# MCU.net
KiCad netlist of a schematic drawn in Altium Designer
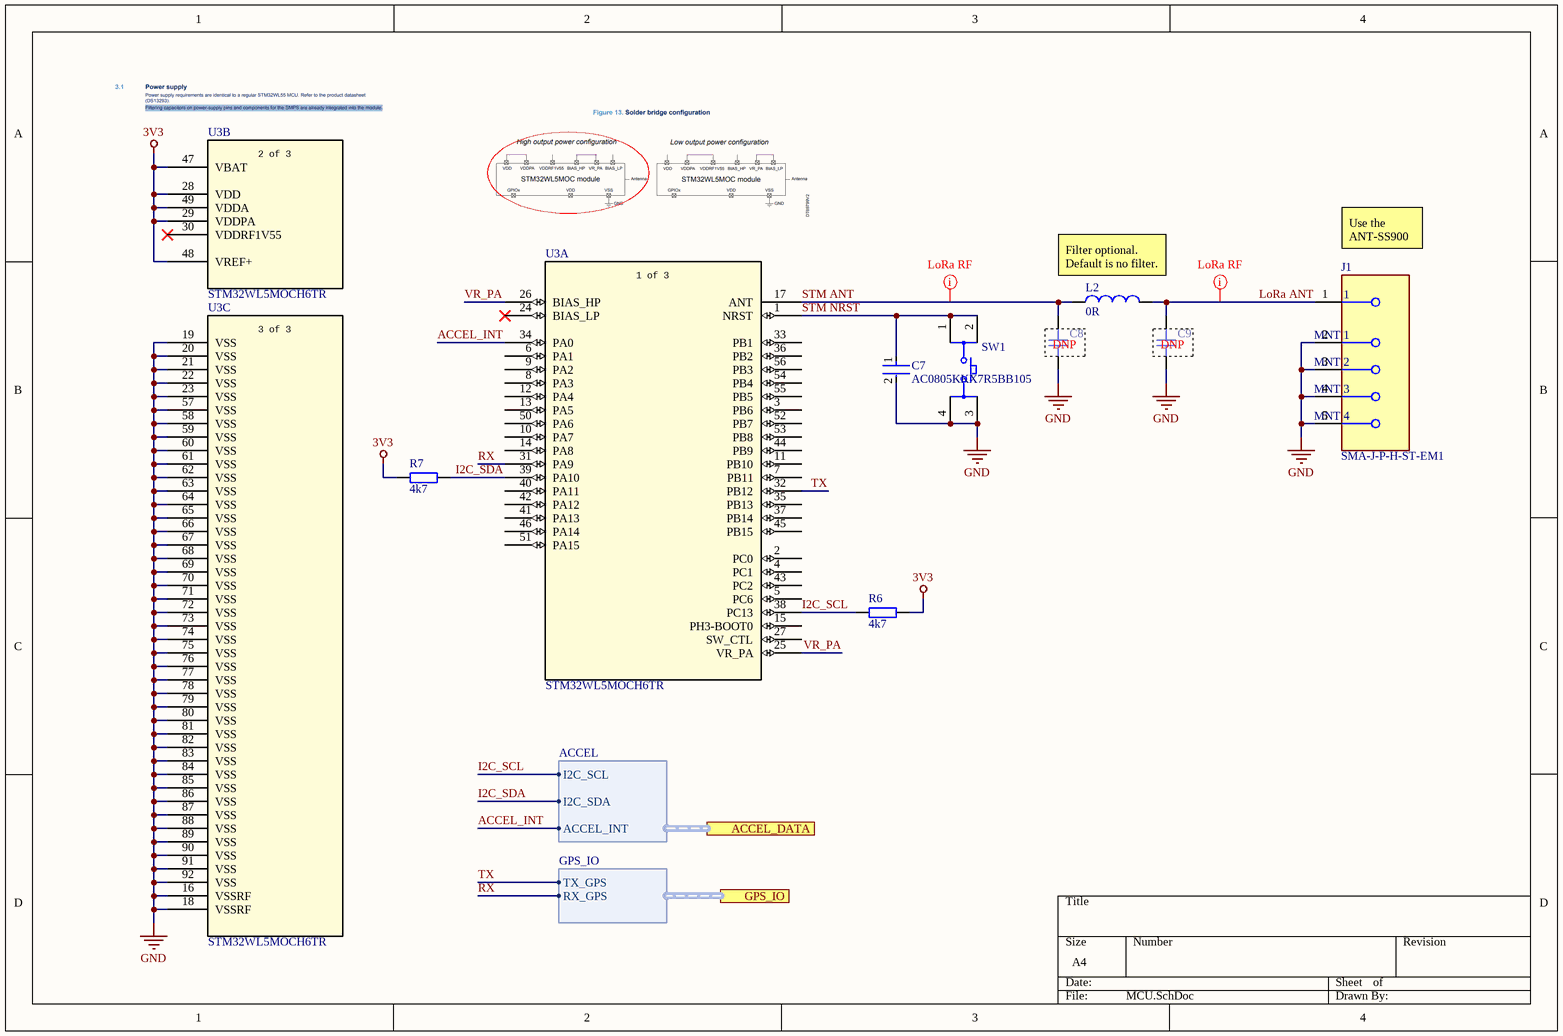
[diagram p0: MCU.SchDoc]

(export (version "E")
  (design (tool "Eeschema 10.0.6"))
  (components
    (comp (ref "C7")
      (value "AC0805KKX7R5BB105")
      (footprint "FP-AC0805-0_85-MFG")
      (description "AC0805 1 uF X7R 10.00% 6.3 V")
      (fields
        (field (name "OCTOPART") "https://octopart.com/ac0805kkx7r5bb105-yageo-78873385")
        (field (name "TOLERANCE") "0.1")
      )
      (libsource (lib "Altium Content Vault") (part "11868f565c42a9108669ba33697ecf6"))
    )
    (comp (ref "C8")
      (value "~")
      (footprint "CAP_0603")
      (description "Capacitor SMD 0603\r\nCeramic")
      (libsource (lib "Generic library") (part "CAP_0603"))
    )
    (comp (ref "C9")
      (value "~")
      (footprint "CAP_0603")
      (description "Capacitor SMD 0603\r\nCeramic")
      (libsource (lib "Generic library") (part "CAP_0603"))
    )
    (comp (ref "J1")
      (value "SMA-J-P-H-ST-EM1")
      (footprint "FP-SMA-J-P-H-ST-EM1-MFG")
      (description "CONN SMA JACK STR 50OHM EDGE MNT\r\nUse the ANT-SS900")
      (libsource (lib "Schlib1") (part "LoRa antenna connector"))
    )
    (comp (ref "L2")
      (value "0R")
      (footprint "CAP_0603")
      (description "Not necessary. Place 0 ohm resistor")
      (fields (field (name "MP") "LQG18HN27NJ00D"))
      (libsource (lib "Schlib1") (part "Inductor"))
    )
    (comp (ref "R6")
      (value "4k7")
      (footprint "RES_0603")
      (description "Resistor SMD 0603")
      (libsource (lib "Generic library") (part "RES_0603"))
    )
    (comp (ref "R7")
      (value "4k7")
      (footprint "RES_0603")
      (description "Resistor SMD 0603")
      (libsource (lib "Generic library") (part "RES_0603"))
    )
    (comp (ref "SW1")
      (value "TL3301AF160QG")
      (footprint "FP-TL3301AF160QG-MFG")
      (description "SWITCH TACTILE SPST-NO 0.05A 12V")
      (libsource (lib "Altium Content Vault") (part "94cebf9f54af8bed749b87481745719"))
    )
    (comp (ref "U3")
      (value "STM32WL5MOCH6TR")
      (footprint "LGA-92_10X10_STM")
      (description "Multiprotocol LPWAN dual-core module 32-bit Arm Cortex-M4/M0+ LoRa,(G)FSK, (G)MSK, BPSK")
      (fields (field (name "COPYRIGHT") "Copyright (C) 2026 Ultra Librarian. All rights reserved."))
      (libsource (lib "") (part "STM32WL5MOCH6TR_1"))
    )
  )
  (nets
    (net (code "3") (name "/ACCEL_INT") (class "Default")
      (node (ref "U3") (pin "34") (pinfunction "PA0_34") (pintype "bidirectional"))
    )
    (net (code "4") (name "/I2C_SCL") (class "Default")
      (node (ref "R6") (pin "1") (pinfunction "1_1") (pintype "passive"))
      (node (ref "U3") (pin "38") (pinfunction "PC13_38") (pintype "bidirectional"))
    )
    (net (code "5") (name "/I2C_SDA") (class "Default")
      (node (ref "R7") (pin "1") (pinfunction "1_1") (pintype "passive"))
      (node (ref "U3") (pin "39") (pinfunction "PA10_39") (pintype "bidirectional"))
    )
    (net (code "6") (name "/LoRa ANT") (class "Default")
      (node (ref "C9") (pin "2") (pinfunction "2_2") (pintype "passive"))
      (node (ref "J1") (pin "1") (pinfunction "1_1") (pintype "passive"))
      (node (ref "L2") (pin "2") (pinfunction "2_2") (pintype "passive"))
    )
    (net (code "7") (name "/RX") (class "Default")
      (node (ref "U3") (pin "31") (pinfunction "PA9_31") (pintype "bidirectional"))
    )
    (net (code "8") (name "/STM ANT") (class "Default")
      (node (ref "C8") (pin "2") (pinfunction "2_2") (pintype "passive"))
      (node (ref "L2") (pin "1") (pinfunction "1_1") (pintype "passive"))
      (node (ref "U3") (pin "17") (pinfunction "ANT_17") (pintype "passive"))
    )
    (net (code "9") (name "/STM NRST") (class "Default")
      (node (ref "C7") (pin "1") (pinfunction "1_1") (pintype "passive"))
      (node (ref "SW1") (pin "1") (pinfunction "1_1") (pintype "passive"))
      (node (ref "SW1") (pin "2") (pinfunction "2_2") (pintype "passive"))
      (node (ref "U3") (pin "1") (pinfunction "NRST_1") (pintype "bidirectional"))
    )
    (net (code "10") (name "/TX") (class "Default")
      (node (ref "U3") (pin "32") (pinfunction "PB12_32") (pintype "bidirectional"))
    )
    (net (code "11") (name "/VR_PA") (class "Default")
      (node (ref "U3") (pin "25") (pinfunction "VR_PA_25") (pintype "bidirectional"))
      (node (ref "U3") (pin "26") (pinfunction "BIAS_HP_26") (pintype "bidirectional"))
    )
    (net (code "14") (name "3V3") (class "Default")
      (node (ref "R6") (pin "2") (pinfunction "2_2") (pintype "passive"))
      (node (ref "R7") (pin "2") (pinfunction "2_2") (pintype "passive"))
      (node (ref "U3") (pin "28") (pinfunction "VDD_28") (pintype "power_in"))
      (node (ref "U3") (pin "29") (pinfunction "VDDPA_29") (pintype "power_in"))
      (node (ref "U3") (pin "47") (pinfunction "VBAT_47") (pintype "power_in"))
      (node (ref "U3") (pin "48") (pinfunction "VREF+_48") (pintype "power_in"))
      (node (ref "U3") (pin "49") (pinfunction "VDDA_49") (pintype "power_in"))
    )
    (net (code "15") (name "GND") (class "Default")
      (node (ref "C7") (pin "2") (pinfunction "2_2") (pintype "passive"))
      (node (ref "C8") (pin "1") (pinfunction "1_1") (pintype "passive"))
      (node (ref "C9") (pin "1") (pinfunction "1_1") (pintype "passive"))
      (node (ref "J1") (pin "2") (pinfunction "MNT_1_2") (pintype "passive"))
      (node (ref "J1") (pin "3") (pinfunction "MNT_2_3") (pintype "passive"))
      (node (ref "J1") (pin "4") (pinfunction "MNT_3_4") (pintype "passive"))
      (node (ref "J1") (pin "5") (pinfunction "MNT_4_5") (pintype "passive"))
      (node (ref "SW1") (pin "3") (pinfunction "3_3") (pintype "passive"))
      (node (ref "SW1") (pin "4") (pinfunction "4_4") (pintype "passive"))
      (node (ref "U3") (pin "16") (pinfunction "VSSRF_16") (pintype "power_in"))
      (node (ref "U3") (pin "18") (pinfunction "VSSRF_18") (pintype "power_in"))
      (node (ref "U3") (pin "19") (pinfunction "VSS_19") (pintype "power_in"))
      (node (ref "U3") (pin "20") (pinfunction "VSS_20") (pintype "power_in"))
      (node (ref "U3") (pin "21") (pinfunction "VSS_21") (pintype "power_in"))
      (node (ref "U3") (pin "22") (pinfunction "VSS_22") (pintype "power_in"))
      (node (ref "U3") (pin "23") (pinfunction "VSS_23") (pintype "power_in"))
      (node (ref "U3") (pin "57") (pinfunction "VSS_57") (pintype "power_in"))
      (node (ref "U3") (pin "58") (pinfunction "VSS_58") (pintype "power_in"))
      (node (ref "U3") (pin "59") (pinfunction "VSS_59") (pintype "power_in"))
      (node (ref "U3") (pin "60") (pinfunction "VSS_60") (pintype "power_in"))
      (node (ref "U3") (pin "61") (pinfunction "VSS_61") (pintype "power_in"))
      (node (ref "U3") (pin "62") (pinfunction "VSS_62") (pintype "power_in"))
      (node (ref "U3") (pin "63") (pinfunction "VSS_63") (pintype "power_in"))
      (node (ref "U3") (pin "64") (pinfunction "VSS_64") (pintype "power_in"))
      (node (ref "U3") (pin "65") (pinfunction "VSS_65") (pintype "power_in"))
      (node (ref "U3") (pin "66") (pinfunction "VSS_66") (pintype "power_in"))
      (node (ref "U3") (pin "67") (pinfunction "VSS_67") (pintype "power_in"))
      (node (ref "U3") (pin "68") (pinfunction "VSS_68") (pintype "power_in"))
      (node (ref "U3") (pin "69") (pinfunction "VSS_69") (pintype "power_in"))
      (node (ref "U3") (pin "70") (pinfunction "VSS_70") (pintype "power_in"))
      (node (ref "U3") (pin "71") (pinfunction "VSS_71") (pintype "power_in"))
      (node (ref "U3") (pin "72") (pinfunction "VSS_72") (pintype "power_in"))
      (node (ref "U3") (pin "73") (pinfunction "VSS_73") (pintype "power_in"))
      (node (ref "U3") (pin "74") (pinfunction "VSS_74") (pintype "power_in"))
      (node (ref "U3") (pin "75") (pinfunction "VSS_75") (pintype "power_in"))
      (node (ref "U3") (pin "76") (pinfunction "VSS_76") (pintype "power_in"))
      (node (ref "U3") (pin "77") (pinfunction "VSS_77") (pintype "power_in"))
      (node (ref "U3") (pin "78") (pinfunction "VSS_78") (pintype "power_in"))
      (node (ref "U3") (pin "79") (pinfunction "VSS_79") (pintype "power_in"))
      (node (ref "U3") (pin "80") (pinfunction "VSS_80") (pintype "power_in"))
      (node (ref "U3") (pin "81") (pinfunction "VSS_81") (pintype "power_in"))
      (node (ref "U3") (pin "82") (pinfunction "VSS_82") (pintype "power_in"))
      (node (ref "U3") (pin "83") (pinfunction "VSS_83") (pintype "power_in"))
      (node (ref "U3") (pin "84") (pinfunction "VSS_84") (pintype "power_in"))
      (node (ref "U3") (pin "85") (pinfunction "VSS_85") (pintype "power_in"))
      (node (ref "U3") (pin "86") (pinfunction "VSS_86") (pintype "power_in"))
      (node (ref "U3") (pin "87") (pinfunction "VSS_87") (pintype "power_in"))
      (node (ref "U3") (pin "88") (pinfunction "VSS_88") (pintype "power_in"))
      (node (ref "U3") (pin "89") (pinfunction "VSS_89") (pintype "power_in"))
      (node (ref "U3") (pin "90") (pinfunction "VSS_90") (pintype "power_in"))
      (node (ref "U3") (pin "91") (pinfunction "VSS_91") (pintype "power_in"))
      (node (ref "U3") (pin "92") (pinfunction "VSS_92") (pintype "power_in"))
    )
    (net (code "16") (name "unconnected-(U3A-BIAS_LP-Pad24)") (class "Default")
      (node (ref "U3") (pin "24") (pinfunction "BIAS_LP_24") (pintype "bidirectional+no_connect"))
    )
    (net (code "17") (name "unconnected-(U3A-PA1-Pad6)") (class "Default")
      (node (ref "U3") (pin "6") (pinfunction "PA1_6") (pintype "bidirectional"))
    )
    (net (code "18") (name "unconnected-(U3A-PA2-Pad9)") (class "Default")
      (node (ref "U3") (pin "9") (pinfunction "PA2_9") (pintype "bidirectional"))
    )
    (net (code "19") (name "unconnected-(U3A-PA3-Pad8)") (class "Default")
      (node (ref "U3") (pin "8") (pinfunction "PA3_8") (pintype "bidirectional"))
    )
    (net (code "20") (name "unconnected-(U3A-PA4-Pad12)") (class "Default")
      (node (ref "U3") (pin "12") (pinfunction "PA4_12") (pintype "bidirectional"))
    )
    (net (code "21") (name "unconnected-(U3A-PA5-Pad13)") (class "Default")
      (node (ref "U3") (pin "13") (pinfunction "PA5_13") (pintype "bidirectional"))
    )
    (net (code "22") (name "unconnected-(U3A-PA6-Pad50)") (class "Default")
      (node (ref "U3") (pin "50") (pinfunction "PA6_50") (pintype "bidirectional"))
    )
    (net (code "23") (name "unconnected-(U3A-PA7-Pad10)") (class "Default")
      (node (ref "U3") (pin "10") (pinfunction "PA7_10") (pintype "bidirectional"))
    )
    (net (code "24") (name "unconnected-(U3A-PA8-Pad14)") (class "Default")
      (node (ref "U3") (pin "14") (pinfunction "PA8_14") (pintype "bidirectional"))
    )
    (net (code "25") (name "unconnected-(U3A-PA11-Pad40)") (class "Default")
      (node (ref "U3") (pin "40") (pinfunction "PA11_40") (pintype "bidirectional"))
    )
    (net (code "26") (name "unconnected-(U3A-PA12-Pad42)") (class "Default")
      (node (ref "U3") (pin "42") (pinfunction "PA12_42") (pintype "bidirectional"))
    )
    (net (code "27") (name "unconnected-(U3A-PA13-Pad41)") (class "Default")
      (node (ref "U3") (pin "41") (pinfunction "PA13_41") (pintype "bidirectional"))
    )
    (net (code "28") (name "unconnected-(U3A-PA14-Pad46)") (class "Default")
      (node (ref "U3") (pin "46") (pinfunction "PA14_46") (pintype "bidirectional"))
    )
    (net (code "29") (name "unconnected-(U3A-PA15-Pad51)") (class "Default")
      (node (ref "U3") (pin "51") (pinfunction "PA15_51") (pintype "bidirectional"))
    )
    (net (code "30") (name "unconnected-(U3A-PB1-Pad33)") (class "Default")
      (node (ref "U3") (pin "33") (pinfunction "PB1_33") (pintype "bidirectional"))
    )
    (net (code "31") (name "unconnected-(U3A-PB2-Pad36)") (class "Default")
      (node (ref "U3") (pin "36") (pinfunction "PB2_36") (pintype "bidirectional"))
    )
    (net (code "32") (name "unconnected-(U3A-PB3-Pad56)") (class "Default")
      (node (ref "U3") (pin "56") (pinfunction "PB3_56") (pintype "bidirectional"))
    )
    (net (code "33") (name "unconnected-(U3A-PB4-Pad54)") (class "Default")
      (node (ref "U3") (pin "54") (pinfunction "PB4_54") (pintype "bidirectional"))
    )
    (net (code "34") (name "unconnected-(U3A-PB5-Pad55)") (class "Default")
      (node (ref "U3") (pin "55") (pinfunction "PB5_55") (pintype "bidirectional"))
    )
    (net (code "35") (name "unconnected-(U3A-PB6-Pad3)") (class "Default")
      (node (ref "U3") (pin "3") (pinfunction "PB6_3") (pintype "bidirectional"))
    )
    (net (code "36") (name "unconnected-(U3A-PB7-Pad52)") (class "Default")
      (node (ref "U3") (pin "52") (pinfunction "PB7_52") (pintype "bidirectional"))
    )
    (net (code "37") (name "unconnected-(U3A-PB8-Pad53)") (class "Default")
      (node (ref "U3") (pin "53") (pinfunction "PB8_53") (pintype "bidirectional"))
    )
    (net (code "38") (name "unconnected-(U3A-PB9-Pad44)") (class "Default")
      (node (ref "U3") (pin "44") (pinfunction "PB9_44") (pintype "bidirectional"))
    )
    (net (code "39") (name "unconnected-(U3A-PB10-Pad11)") (class "Default")
      (node (ref "U3") (pin "11") (pinfunction "PB10_11") (pintype "bidirectional"))
    )
    (net (code "40") (name "unconnected-(U3A-PB11-Pad7)") (class "Default")
      (node (ref "U3") (pin "7") (pinfunction "PB11_7") (pintype "bidirectional"))
    )
    (net (code "41") (name "unconnected-(U3A-PB13-Pad35)") (class "Default")
      (node (ref "U3") (pin "35") (pinfunction "PB13_35") (pintype "bidirectional"))
    )
    (net (code "42") (name "unconnected-(U3A-PB14-Pad37)") (class "Default")
      (node (ref "U3") (pin "37") (pinfunction "PB14_37") (pintype "bidirectional"))
    )
    (net (code "43") (name "unconnected-(U3A-PB15-Pad45)") (class "Default")
      (node (ref "U3") (pin "45") (pinfunction "PB15_45") (pintype "bidirectional"))
    )
    (net (code "44") (name "unconnected-(U3A-PC0-Pad2)") (class "Default")
      (node (ref "U3") (pin "2") (pinfunction "PC0_2") (pintype "bidirectional"))
    )
    (net (code "45") (name "unconnected-(U3A-PC1-Pad4)") (class "Default")
      (node (ref "U3") (pin "4") (pinfunction "PC1_4") (pintype "bidirectional"))
    )
    (net (code "46") (name "unconnected-(U3A-PC2-Pad43)") (class "Default")
      (node (ref "U3") (pin "43") (pinfunction "PC2_43") (pintype "bidirectional"))
    )
    (net (code "47") (name "unconnected-(U3A-PC6-Pad5)") (class "Default")
      (node (ref "U3") (pin "5") (pinfunction "PC6_5") (pintype "bidirectional"))
    )
    (net (code "48") (name "unconnected-(U3A-PH3-BOOT0-Pad15)") (class "Default")
      (node (ref "U3") (pin "15") (pinfunction "PH3-BOOT0_15") (pintype "bidirectional"))
    )
    (net (code "49") (name "unconnected-(U3A-SW_CTL-Pad27)") (class "Default")
      (node (ref "U3") (pin "27") (pinfunction "SW_CTL_27") (pintype "bidirectional"))
    )
    (net (code "50") (name "unconnected-(U3B-VDDRF1V55-Pad30)") (class "Default")
      (node (ref "U3") (pin "30") (pinfunction "VDDRF1V55_30") (pintype "power_in+no_connect"))
    )
  )
)
